# robot2_-_version_pro.net
KiCad netlist of a schematic drawn in EAGLE
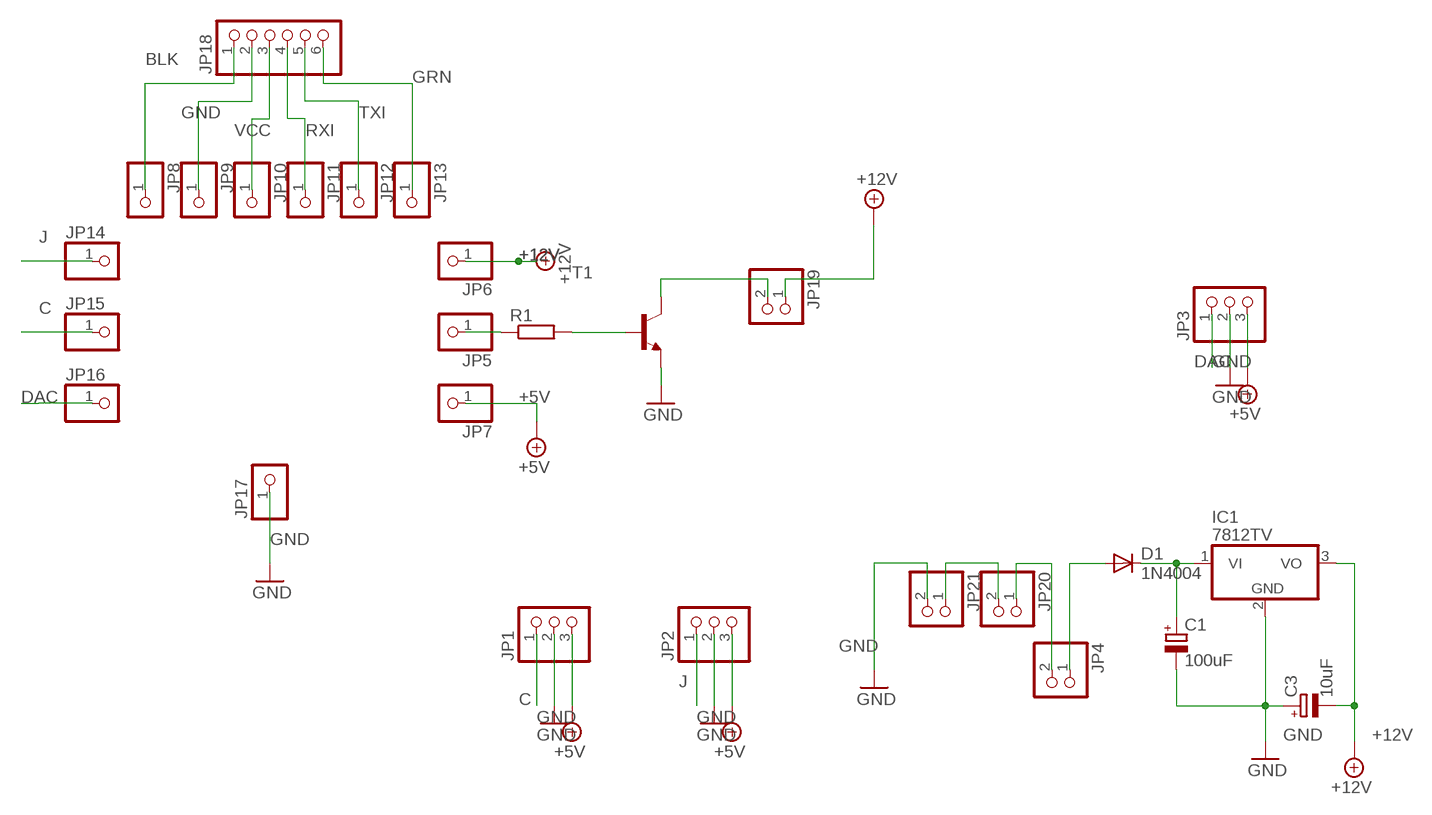
[diagram p0: schematic, sheet 1]

(export (version "E")
  (design (tool "Eeschema 10.0.6"))
  (components
    (comp (ref "C1")
      (value "100uF")
      (footprint "eagle-import:E3,5-10")
      (libsource (lib "eagle-import") (part "CPOL-EUE3.5-10"))
    )
    (comp (ref "C3")
      (value "10uF")
      (footprint "eagle-import:E2,5-6E")
      (libsource (lib "eagle-import") (part "CPOL-EUE2,5-6E"))
    )
    (comp (ref "D1")
      (value "1N4004")
      (footprint "eagle-import:DO41-10")
      (libsource (lib "eagle-import") (part "1N4004"))
    )
    (comp (ref "IC1")
      (value "7812TV")
      (footprint "eagle-import:TO220V")
      (libsource (lib "eagle-import") (part "78TV12"))
    )
    (comp (ref "JP1")
      (value "PINHD-1X3")
      (footprint "eagle-import:1X03")
      (libsource (lib "eagle-import") (part "PINHD-1X3"))
    )
    (comp (ref "JP2")
      (value "PINHD-1X3")
      (footprint "eagle-import:1X03")
      (libsource (lib "eagle-import") (part "PINHD-1X3"))
    )
    (comp (ref "JP3")
      (value "PINHD-1X3")
      (footprint "eagle-import:1X03")
      (libsource (lib "eagle-import") (part "PINHD-1X3"))
    )
    (comp (ref "JP4")
      (value "PINHD-1X2")
      (footprint "eagle-import:1X02")
      (libsource (lib "eagle-import") (part "PINHD-1X2"))
    )
    (comp (ref "JP5")
      (value "PINHD-1X1")
      (footprint "eagle-import:1X01")
      (libsource (lib "eagle-import") (part "PINHD-1X1"))
    )
    (comp (ref "JP6")
      (value "PINHD-1X1")
      (footprint "eagle-import:1X01")
      (libsource (lib "eagle-import") (part "PINHD-1X1"))
    )
    (comp (ref "JP7")
      (value "PINHD-1X1")
      (footprint "eagle-import:1X01")
      (libsource (lib "eagle-import") (part "PINHD-1X1"))
    )
    (comp (ref "JP8")
      (value "PINHD-1X1")
      (footprint "eagle-import:1X01")
      (libsource (lib "eagle-import") (part "PINHD-1X1"))
    )
    (comp (ref "JP9")
      (value "PINHD-1X1")
      (footprint "eagle-import:1X01")
      (libsource (lib "eagle-import") (part "PINHD-1X1"))
    )
    (comp (ref "JP10")
      (value "PINHD-1X1")
      (footprint "eagle-import:1X01")
      (libsource (lib "eagle-import") (part "PINHD-1X1"))
    )
    (comp (ref "JP11")
      (value "PINHD-1X1")
      (footprint "eagle-import:1X01")
      (libsource (lib "eagle-import") (part "PINHD-1X1"))
    )
    (comp (ref "JP12")
      (value "PINHD-1X1")
      (footprint "eagle-import:1X01")
      (libsource (lib "eagle-import") (part "PINHD-1X1"))
    )
    (comp (ref "JP13")
      (value "PINHD-1X1")
      (footprint "eagle-import:1X01")
      (libsource (lib "eagle-import") (part "PINHD-1X1"))
    )
    (comp (ref "JP14")
      (value "PINHD-1X1")
      (footprint "eagle-import:1X01")
      (libsource (lib "eagle-import") (part "PINHD-1X1"))
    )
    (comp (ref "JP15")
      (value "PINHD-1X1")
      (footprint "eagle-import:1X01")
      (libsource (lib "eagle-import") (part "PINHD-1X1"))
    )
    (comp (ref "JP16")
      (value "PINHD-1X1")
      (footprint "eagle-import:1X01")
      (libsource (lib "eagle-import") (part "PINHD-1X1"))
    )
    (comp (ref "JP17")
      (value "PINHD-1X1")
      (footprint "eagle-import:1X01")
      (libsource (lib "eagle-import") (part "PINHD-1X1"))
    )
    (comp (ref "JP18")
      (value "PINHD-1X6")
      (footprint "eagle-import:1X06")
      (libsource (lib "eagle-import") (part "PINHD-1X6"))
    )
    (comp (ref "JP19")
      (value "PINHD-1X2")
      (footprint "eagle-import:1X02")
      (libsource (lib "eagle-import") (part "PINHD-1X2"))
    )
    (comp (ref "JP20")
      (value "PINHD-1X2")
      (footprint "eagle-import:1X02")
      (libsource (lib "eagle-import") (part "PINHD-1X2"))
    )
    (comp (ref "JP21")
      (value "PINHD-1X2")
      (footprint "eagle-import:1X02")
      (libsource (lib "eagle-import") (part "PINHD-1X2"))
    )
    (comp (ref "R1")
      (value "R-EU_0204/7")
      (footprint "eagle-import:0204_7")
      (libsource (lib "eagle-import") (part "R-EU_0204/7"))
    )
    (comp (ref "T1")
      (value "2N4124-NPN-TO92-CBE")
      (footprint "eagle-import:TO92-CBE")
      (libsource (lib "eagle-import") (part "-NPN-TO92-CBE2N4124"))
    )
  )
  (nets
    (net (code "1") (name "+5V") (class "Default")
      (node (ref "JP1") (pin "3") (pinfunction "3_3") (pintype "passive"))
      (node (ref "JP2") (pin "3") (pinfunction "3_3") (pintype "passive"))
      (node (ref "JP3") (pin "3") (pinfunction "3_3") (pintype "passive"))
      (node (ref "JP7") (pin "1") (pinfunction "1_1") (pintype "passive"))
    )
    (net (code "2") (name "+12V") (class "Default")
      (node (ref "C3") (pin "-") (pinfunction "-_-") (pintype "passive"))
      (node (ref "IC1") (pin "3") (pinfunction "VO_3") (pintype "passive"))
      (node (ref "JP19") (pin "1") (pinfunction "1_1") (pintype "passive"))
      (node (ref "JP6") (pin "1") (pinfunction "1_1") (pintype "passive"))
    )
    (net (code "3") (name "/BLK") (class "Default")
      (node (ref "JP18") (pin "1") (pinfunction "1_1") (pintype "passive"))
      (node (ref "JP8") (pin "1") (pinfunction "1_1") (pintype "passive"))
    )
    (net (code "4") (name "/C") (class "Default")
      (node (ref "JP1") (pin "1") (pinfunction "1_1") (pintype "passive"))
      (node (ref "JP15") (pin "1") (pinfunction "1_1") (pintype "passive"))
    )
    (net (code "5") (name "/DAC") (class "Default")
      (node (ref "JP16") (pin "1") (pinfunction "1_1") (pintype "passive"))
      (node (ref "JP3") (pin "1") (pinfunction "1_1") (pintype "passive"))
    )
    (net (code "6") (name "/GRN") (class "Default")
      (node (ref "JP13") (pin "1") (pinfunction "1_1") (pintype "passive"))
      (node (ref "JP18") (pin "6") (pinfunction "6_6") (pintype "passive"))
    )
    (net (code "7") (name "/J") (class "Default")
      (node (ref "JP14") (pin "1") (pinfunction "1_1") (pintype "passive"))
      (node (ref "JP2") (pin "1") (pinfunction "1_1") (pintype "passive"))
    )
    (net (code "8") (name "/RXI") (class "Default")
      (node (ref "JP11") (pin "1") (pinfunction "1_1") (pintype "passive"))
      (node (ref "JP18") (pin "4") (pinfunction "4_4") (pintype "passive"))
    )
    (net (code "9") (name "/TXI") (class "Default")
      (node (ref "JP12") (pin "1") (pinfunction "1_1") (pintype "passive"))
      (node (ref "JP18") (pin "5") (pinfunction "5_5") (pintype "passive"))
    )
    (net (code "10") (name "/VCC") (class "Default")
      (node (ref "JP10") (pin "1") (pinfunction "1_1") (pintype "passive"))
      (node (ref "JP18") (pin "3") (pinfunction "3_3") (pintype "passive"))
    )
    (net (code "11") (name "GND") (class "Default")
      (node (ref "C1") (pin "-") (pinfunction "-_-") (pintype "passive"))
      (node (ref "C3") (pin "+") (pinfunction "+_+") (pintype "passive"))
      (node (ref "IC1") (pin "2") (pinfunction "GND_2") (pintype "passive"))
      (node (ref "JP1") (pin "2") (pinfunction "2_2") (pintype "passive"))
      (node (ref "JP17") (pin "1") (pinfunction "1_1") (pintype "passive"))
      (node (ref "JP18") (pin "2") (pinfunction "2_2") (pintype "passive"))
      (node (ref "JP2") (pin "2") (pinfunction "2_2") (pintype "passive"))
      (node (ref "JP21") (pin "2") (pinfunction "2_2") (pintype "passive"))
      (node (ref "JP3") (pin "2") (pinfunction "2_2") (pintype "passive"))
      (node (ref "JP9") (pin "1") (pinfunction "1_1") (pintype "passive"))
      (node (ref "T1") (pin "E") (pinfunction "E_E") (pintype "passive"))
    )
    (net (code "12") (name "Net-(D1-PadA)") (class "Default")
      (node (ref "D1") (pin "A") (pinfunction "A_A") (pintype "passive"))
      (node (ref "JP4") (pin "1") (pinfunction "1_1") (pintype "passive"))
    )
    (net (code "13") (name "Net-(IC1-VI)") (class "Default")
      (node (ref "C1") (pin "+") (pinfunction "+_+") (pintype "passive"))
      (node (ref "D1") (pin "C") (pinfunction "C_C") (pintype "passive"))
      (node (ref "IC1") (pin "1") (pinfunction "VI_1") (pintype "input"))
    )
    (net (code "14") (name "Net-(JP5-Pad1)") (class "Default")
      (node (ref "JP5") (pin "1") (pinfunction "1_1") (pintype "passive"))
      (node (ref "R1") (pin "1") (pinfunction "1_1") (pintype "passive"))
    )
    (net (code "15") (name "Net-(JP19-Pad2)") (class "Default")
      (node (ref "JP19") (pin "2") (pinfunction "2_2") (pintype "passive"))
      (node (ref "T1") (pin "C") (pinfunction "C_C") (pintype "passive"))
    )
    (net (code "16") (name "Net-(JP20-Pad1)") (class "Default")
      (node (ref "JP20") (pin "1") (pinfunction "1_1") (pintype "passive"))
      (node (ref "JP4") (pin "2") (pinfunction "2_2") (pintype "passive"))
    )
    (net (code "17") (name "Net-(JP20-Pad2)") (class "Default")
      (node (ref "JP20") (pin "2") (pinfunction "2_2") (pintype "passive"))
      (node (ref "JP21") (pin "1") (pinfunction "1_1") (pintype "passive"))
    )
    (net (code "18") (name "Net-(R1-Pad2)") (class "Default")
      (node (ref "R1") (pin "2") (pinfunction "2_2") (pintype "passive"))
      (node (ref "T1") (pin "B") (pinfunction "B_B") (pintype "passive"))
    )
  )
)
